# UPCNSL-ABS-FLS-RFS.net
KiCad netlist of a schematic drawn in Altium Designer
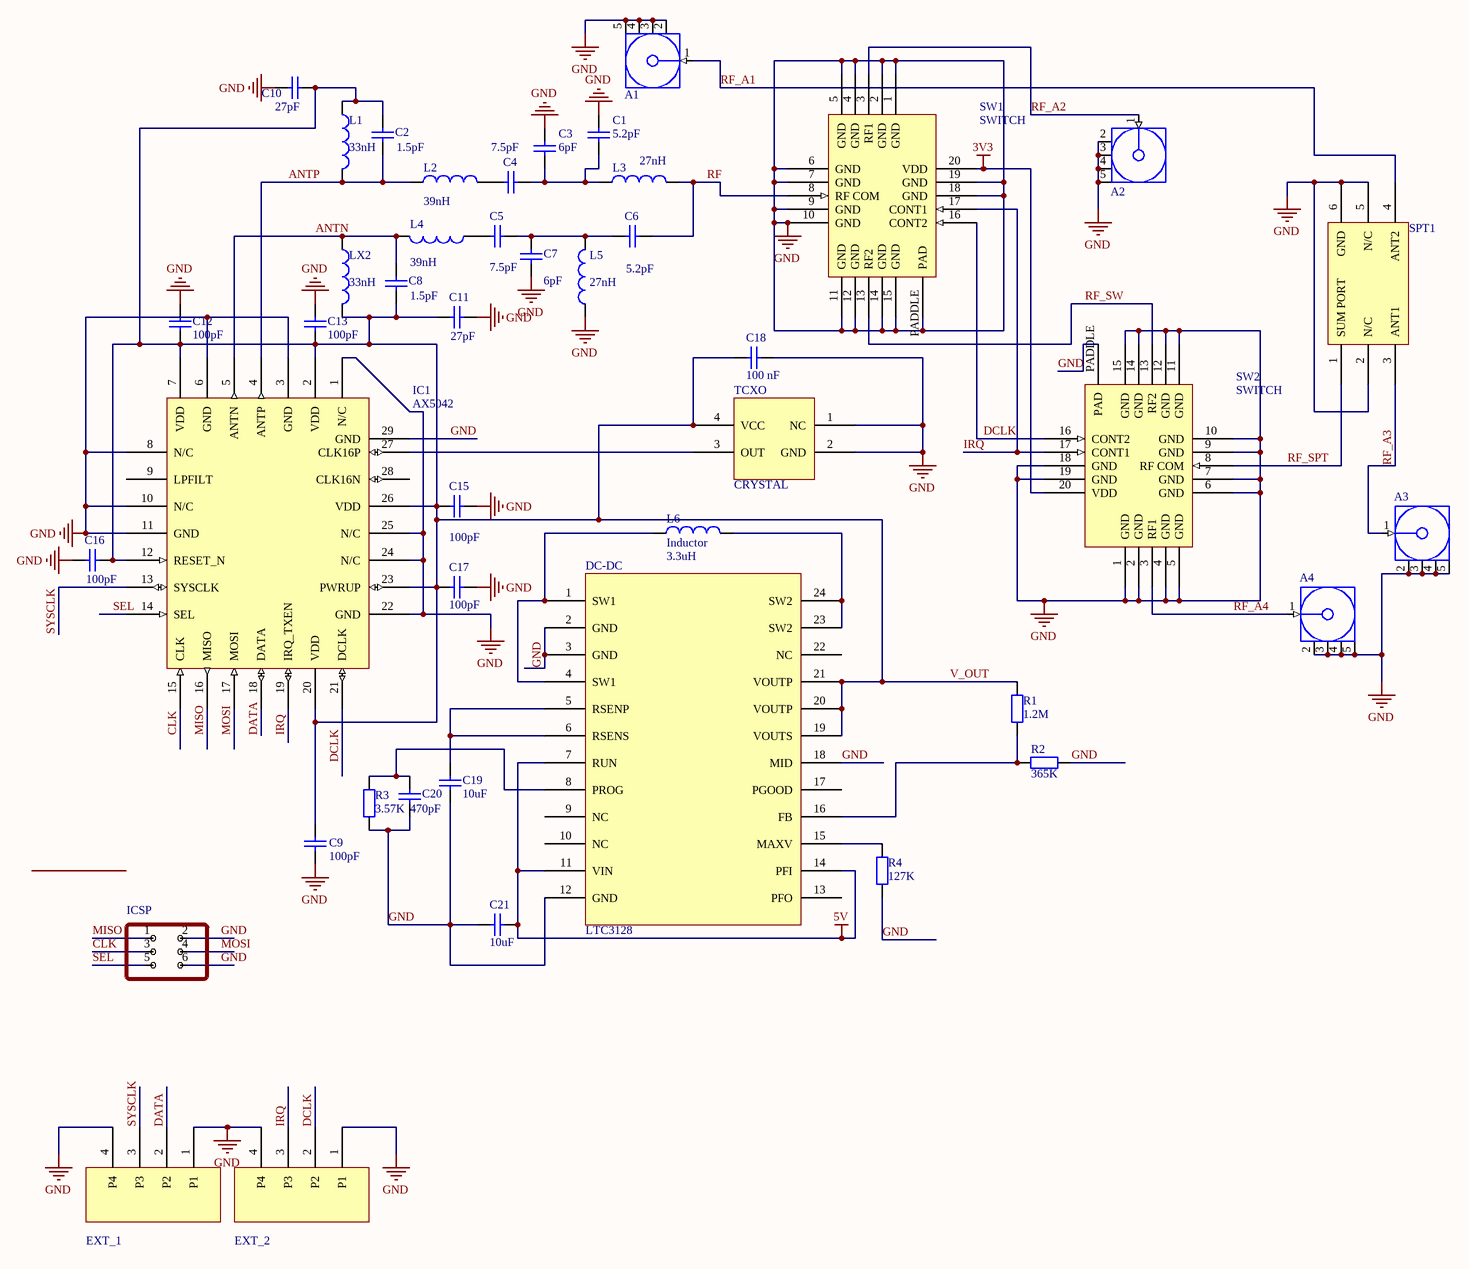
[diagram p0: UPCNSL-ABS-FLS-RFS.SchDoc]

(export (version "E")
  (design (tool "Eeschema 10.0.6"))
  (components
    (comp (ref "A1")
      (value "ANTENNA")
      (footprint "MCX5.08-H5")
      (fields (field (name "PUBLISHER") "Altium Limited"))
      (libsource (lib "Miscellaneous Connectors") (part "COAX-F"))
    )
    (comp (ref "A2")
      (value "SORTIDA AMP EXTERN")
      (footprint "MCX5.08-H5")
      (fields (field (name "PUBLISHER") "Altium Limited"))
      (libsource (lib "Miscellaneous Connectors") (part "COAX-F"))
    )
    (comp (ref "A3")
      (value "ANTENNA")
      (footprint "MCX5.08-H5")
      (fields (field (name "PUBLISHER") "Altium Limited"))
      (libsource (lib "Miscellaneous Connectors") (part "COAX-F"))
    )
    (comp (ref "A4")
      (value "ENTRADA AMP EXTERN")
      (footprint "MCX5.08-H5")
      (fields (field (name "PUBLISHER") "Altium Limited"))
      (libsource (lib "Miscellaneous Connectors") (part "COAX-F"))
    )
    (comp (ref "C1")
      (value "5.2pF")
      (footprint "CAP0603")
      (description "Capacitor")
      (fields (field (name "Comment") "CB1") (field (name "PUBLISHER") "Altium Limited"))
      (libsource (lib "Miscellaneous Devices") (part "Cap"))
    )
    (comp (ref "C2")
      (value "1.5pF")
      (footprint "CAP0603")
      (description "Capacitor")
      (fields (field (name "Comment") "CC1") (field (name "PUBLISHER") "Altium Limited"))
      (libsource (lib "Miscellaneous Devices") (part "Cap"))
    )
    (comp (ref "C3")
      (value "6pF")
      (footprint "CAP0603")
      (description "Capacitor")
      (fields (field (name "Comment") "CM1") (field (name "PUBLISHER") "Altium Limited"))
      (libsource (lib "Miscellaneous Devices") (part "Cap"))
    )
    (comp (ref "C4")
      (value "7.5pF")
      (footprint "CAP0603")
      (description "Capacitor")
      (fields (field (name "Comment") "CT1") (field (name "PUBLISHER") "Altium Limited"))
      (libsource (lib "Miscellaneous Devices") (part "Cap"))
    )
    (comp (ref "C5")
      (value "7.5pF")
      (footprint "CAP0603")
      (description "Capacitor")
      (fields (field (name "Comment") "CT2") (field (name "PUBLISHER") "Altium Limited"))
      (libsource (lib "Miscellaneous Devices") (part "Cap"))
    )
    (comp (ref "C6")
      (value "5.2pF")
      (footprint "CAP0603")
      (description "Capacitor")
      (fields (field (name "Comment") "CB2") (field (name "PUBLISHER") "Altium Limited"))
      (libsource (lib "Miscellaneous Devices") (part "Cap"))
    )
    (comp (ref "C7")
      (value "6pF")
      (footprint "CAP0603")
      (description "Capacitor")
      (fields (field (name "Comment") "CM2") (field (name "PUBLISHER") "Altium Limited"))
      (libsource (lib "Miscellaneous Devices") (part "Cap"))
    )
    (comp (ref "C8")
      (value "1.5pF")
      (footprint "CAP0603")
      (description "Capacitor")
      (fields (field (name "Comment") "CC2") (field (name "PUBLISHER") "Altium Limited"))
      (libsource (lib "Miscellaneous Devices") (part "Cap"))
    )
    (comp (ref "C9")
      (value "100pF")
      (footprint "CAP0603")
      (description "Capacitor")
      (fields (field (name "Comment") "CV1") (field (name "PUBLISHER") "Altium Limited"))
      (libsource (lib "Miscellaneous Devices") (part "Cap"))
    )
    (comp (ref "C10")
      (value "27pF")
      (footprint "CAP0603")
      (description "Capacitor")
      (fields (field (name "Comment") "Cap") (field (name "PUBLISHER") "Altium Limited"))
      (libsource (lib "Miscellaneous Devices") (part "Cap"))
    )
    (comp (ref "C11")
      (value "27pF")
      (footprint "CAP0603")
      (description "Capacitor")
      (fields (field (name "Comment") "Cap") (field (name "PUBLISHER") "Altium Limited"))
      (libsource (lib "Miscellaneous Devices") (part "Cap"))
    )
    (comp (ref "C12")
      (value "100pF")
      (footprint "CAP0603")
      (description "Capacitor")
      (fields (field (name "Comment") "Cap") (field (name "PUBLISHER") "Altium Limited"))
      (libsource (lib "Miscellaneous Devices") (part "Cap"))
    )
    (comp (ref "C13")
      (value "100pF")
      (footprint "CAP0603")
      (description "Capacitor")
      (fields (field (name "Comment") "Cap") (field (name "PUBLISHER") "Altium Limited"))
      (libsource (lib "Miscellaneous Devices") (part "Cap"))
    )
    (comp (ref "C15")
      (value "100pF")
      (footprint "CAP0603")
      (description "Capacitor")
      (fields (field (name "Comment") "Cap") (field (name "PUBLISHER") "Altium Limited"))
      (libsource (lib "Miscellaneous Devices") (part "Cap"))
    )
    (comp (ref "C16")
      (value "100pF")
      (footprint "CAP0603")
      (description "Capacitor")
      (fields (field (name "Comment") "Cap") (field (name "PUBLISHER") "Altium Limited"))
      (libsource (lib "Miscellaneous Devices") (part "Cap"))
    )
    (comp (ref "C17")
      (value "100pF")
      (footprint "CAP0603")
      (description "Capacitor")
      (fields (field (name "Comment") "Cap") (field (name "PUBLISHER") "Altium Limited"))
      (libsource (lib "Miscellaneous Devices") (part "Cap"))
    )
    (comp (ref "C18")
      (value "100 nF")
      (footprint "CAP0603")
      (description "Capacitor")
      (fields (field (name "Comment") "Cap") (field (name "PUBLISHER") "Altium Limited"))
      (libsource (lib "Miscellaneous Devices") (part "Cap"))
    )
    (comp (ref "C19")
      (value "10uF")
      (footprint "CAP0603")
      (description "Capacitor")
      (fields (field (name "Comment") "CAP0603"))
      (libsource (lib "UPCNSL-ABS-FLS-ARD_v1") (part "CAP0603"))
    )
    (comp (ref "C20")
      (value "470pF")
      (footprint "CAP0603")
      (description "Capacitor")
      (fields (field (name "Comment") "CAP0603"))
      (libsource (lib "UPCNSL-ABS-FLS-ARD_v1") (part "CAP0603"))
    )
    (comp (ref "C21")
      (value "10uF")
      (footprint "CAP0603")
      (description "Capacitor")
      (fields (field (name "Comment") "CAP0603"))
      (libsource (lib "UPCNSL-ABS-FLS-ARD_v1") (part "CAP0603"))
    )
    (comp (ref "DC-DC")
      (value "LTC3128")
      (footprint "DW024 (LTC3128)")
      (libsource (lib "UPCNSL-ABS-FLS-ARD_v1.2") (part "LTC3128"))
    )
    (comp (ref "EXT_1")
      (value "HEADER_CONNECTION")
      (footprint "HEADER_CONNECTION")
      (libsource (lib "UPCNSL-ABS-FLS-ARD_v1.2") (part "HEADER_CONNECTION"))
    )
    (comp (ref "EXT_2")
      (value "HEADER_CONNECTION")
      (footprint "HEADER_CONNECTION")
      (libsource (lib "UPCNSL-ABS-FLS-ARD_v1.2") (part "HEADER_CONNECTION"))
    )
    (comp (ref "IC1")
      (value "AX5042")
      (footprint "AX5042")
      (libsource (lib "UPCNSL-ABS-FLS-RFS") (part "AX5042"))
    )
    (comp (ref "ICSP")
      (value "3X2M")
      (footprint "Header 3x2")
      (description "PIN HEADER")
      (libsource (lib "UPCNSL-ABS-FLS-ARD_v1.2") (part "HEADER 3X2"))
    )
    (comp (ref "L1")
      (value "33nH")
      (footprint "INDUCTOR(1608)")
      (description "Inductor")
      (fields (field (name "Comment") "LX1") (field (name "PUBLISHER") "Altium Limited"))
      (libsource (lib "Miscellaneous Devices") (part "Inductor"))
    )
    (comp (ref "L2")
      (value "39nH")
      (footprint "INDUCTOR(1608)")
      (description "Inductor")
      (fields (field (name "Comment") "LT1") (field (name "PUBLISHER") "Altium Limited"))
      (libsource (lib "Miscellaneous Devices") (part "Inductor"))
    )
    (comp (ref "L3")
      (value "27nH")
      (footprint "INDUCTOR(1608)")
      (description "Inductor")
      (fields (field (name "Comment") "LB2") (field (name "PUBLISHER") "Altium Limited"))
      (libsource (lib "Miscellaneous Devices") (part "Inductor"))
    )
    (comp (ref "L4")
      (value "39nH")
      (footprint "INDUCTOR(1608)")
      (description "Inductor")
      (fields (field (name "Comment") "LT2") (field (name "PUBLISHER") "Altium Limited"))
      (libsource (lib "Miscellaneous Devices") (part "Inductor"))
    )
    (comp (ref "L5")
      (value "27nH")
      (footprint "INDUCTOR(1608)")
      (description "Inductor")
      (fields (field (name "Comment") "LB1") (field (name "PUBLISHER") "Altium Limited"))
      (libsource (lib "Miscellaneous Devices") (part "Inductor"))
    )
    (comp (ref "L6")
      (value "Inductor")
      (footprint "INDUCTOR(1608)")
      (fields (field (name "ALTIUM_VALUE") "3.3uH") (field (name "PUBLISHER") "Altium Limited"))
      (libsource (lib "Miscellaneous Devices") (part "Inductor"))
    )
    (comp (ref "LX2")
      (value "33nH")
      (footprint "INDUCTOR(1608)")
      (description "Inductor")
      (fields (field (name "Comment") "LX2") (field (name "PUBLISHER") "Altium Limited"))
      (libsource (lib "Miscellaneous Devices") (part "Inductor"))
    )
    (comp (ref "R1")
      (value "1.2M")
      (footprint "RES0603")
      (description "Resistor")
      (fields (field (name "Comment") "RES0603"))
      (libsource (lib "UPCNSL-ABS-FLS-ARD_v1") (part "RES0603"))
    )
    (comp (ref "R2")
      (value "365K")
      (footprint "RES0603")
      (description "Resistor")
      (fields (field (name "Comment") "RES0603"))
      (libsource (lib "") (part "RES0603_1"))
    )
    (comp (ref "R3")
      (value "3.57K")
      (footprint "RES0603")
      (description "Resistor")
      (fields (field (name "Comment") "RES0603"))
      (libsource (lib "UPCNSL-ABS-FLS-ARD_v1") (part "RES0603"))
    )
    (comp (ref "R4")
      (value "127K")
      (footprint "RES0603")
      (description "Resistor")
      (fields (field (name "Comment") "RES0603"))
      (libsource (lib "UPCNSL-ABS-FLS-ARD_v1") (part "RES0603"))
    )
    (comp (ref "SPT1")
      (value "2 Way -0º split")
      (footprint "SOTFL254P691X411-6N(splitter 2 way-0)")
      (description "Splitter with 0º phase")
      (libsource (lib "Splitters") (part "2 WAY-0º"))
    )
    (comp (ref "SW1")
      (value "SWITCH")
      (footprint "SWITCH")
      (libsource (lib "UPCNSL-ABS-FLS-RFS") (part "SWITCH"))
    )
    (comp (ref "SW2") (value "SWITCH") (footprint "SWITCH") (libsource (lib "") (part "SWITCH_1")))
    (comp (ref "TCXO")
      (value "CRYSTAL")
      (footprint "CRYSTAL TG-5006CJ-24L")
      (libsource (lib "UPCNSL-ABS-FLS-RFS") (part "CRYSTAL"))
    )
  )
  (nets
    (net (code "1") (name "/ANTN") (class "Default")
      (node (ref "C8") (pin "2") (pinfunction "2_2") (pintype "passive"))
      (node (ref "IC1") (pin "5") (pinfunction "ANTN_5") (pintype "output"))
      (node (ref "L4") (pin "2") (pinfunction "2_2") (pintype "passive"))
      (node (ref "LX2") (pin "1") (pinfunction "1_1") (pintype "passive"))
    )
    (net (code "2") (name "/ANTP") (class "Default")
      (node (ref "C2") (pin "1") (pinfunction "1_1") (pintype "passive"))
      (node (ref "IC1") (pin "4") (pinfunction "ANTP_4") (pintype "output"))
      (node (ref "L1") (pin "2") (pinfunction "2_2") (pintype "passive"))
      (node (ref "L2") (pin "1") (pinfunction "1_1") (pintype "passive"))
    )
    (net (code "3") (name "/CLK") (class "Default")
      (node (ref "IC1") (pin "15") (pinfunction "CLK_15") (pintype "input"))
      (node (ref "ICSP") (pin "3") (pinfunction "3_3") (pintype "passive"))
    )
    (net (code "4") (name "/DATA") (class "Default")
      (node (ref "EXT_1") (pin "2") (pinfunction "P2_2") (pintype "passive"))
      (node (ref "IC1") (pin "18") (pinfunction "DATA_18") (pintype "bidirectional"))
    )
    (net (code "5") (name "/DCLK") (class "Default")
      (node (ref "EXT_2") (pin "2") (pinfunction "P2_2") (pintype "passive"))
      (node (ref "IC1") (pin "21") (pinfunction "DCLK_21") (pintype "bidirectional"))
      (node (ref "SW1") (pin "16") (pinfunction "CONT2_16") (pintype "input"))
      (node (ref "SW2") (pin "16") (pinfunction "CONT2_16") (pintype "input"))
    )
    (net (code "6") (name "/IRQ") (class "Default")
      (node (ref "EXT_2") (pin "3") (pinfunction "P3_3") (pintype "passive"))
      (node (ref "IC1") (pin "19") (pinfunction "IRQ_TXEN_19") (pintype "bidirectional"))
      (node (ref "SW1") (pin "17") (pinfunction "CONT1_17") (pintype "input"))
      (node (ref "SW2") (pin "17") (pinfunction "CONT1_17") (pintype "input"))
    )
    (net (code "7") (name "/MISO") (class "Default")
      (node (ref "IC1") (pin "16") (pinfunction "MISO_16") (pintype "output"))
      (node (ref "ICSP") (pin "1") (pinfunction "1_1") (pintype "passive"))
    )
    (net (code "8") (name "/MOSI") (class "Default")
      (node (ref "IC1") (pin "17") (pinfunction "MOSI_17") (pintype "input"))
      (node (ref "ICSP") (pin "4") (pinfunction "4_4") (pintype "passive"))
    )
    (net (code "9") (name "/RF") (class "Default")
      (node (ref "C6") (pin "1") (pinfunction "1_1") (pintype "passive"))
      (node (ref "L3") (pin "2") (pinfunction "2_2") (pintype "passive"))
      (node (ref "SW1") (pin "8") (pinfunction "RF_COM_8") (pintype "input"))
    )
    (net (code "10") (name "/RF_A1") (class "Default")
      (node (ref "A1") (pin "1") (pinfunction "Signal_1") (pintype "input"))
      (node (ref "SPT1") (pin "4") (pinfunction "ANT2_4") (pintype "passive"))
    )
    (net (code "11") (name "/RF_A2") (class "Default")
      (node (ref "A2") (pin "1") (pinfunction "Signal_1") (pintype "input"))
      (node (ref "SW1") (pin "3") (pinfunction "RF1_3") (pintype "passive"))
    )
    (net (code "12") (name "/RF_A3") (class "Default")
      (node (ref "A3") (pin "1") (pinfunction "Signal_1") (pintype "input"))
      (node (ref "SPT1") (pin "3") (pinfunction "ANT1_3") (pintype "passive"))
    )
    (net (code "13") (name "/RF_A4") (class "Default")
      (node (ref "A4") (pin "1") (pinfunction "Signal_1") (pintype "input"))
      (node (ref "SW2") (pin "3") (pinfunction "RF1_3") (pintype "passive"))
    )
    (net (code "14") (name "/RF_SPT") (class "Default")
      (node (ref "SPT1") (pin "1") (pinfunction "SUM_PORT_1") (pintype "passive"))
      (node (ref "SW2") (pin "8") (pinfunction "RF_COM_8") (pintype "input"))
    )
    (net (code "15") (name "/RF_SW") (class "Default")
      (node (ref "SW1") (pin "13") (pinfunction "RF2_13") (pintype "passive"))
      (node (ref "SW2") (pin "13") (pinfunction "RF2_13") (pintype "passive"))
    )
    (net (code "16") (name "/SEL") (class "Default")
      (node (ref "IC1") (pin "14") (pinfunction "SEL_14") (pintype "input"))
      (node (ref "ICSP") (pin "5") (pinfunction "5_5") (pintype "passive"))
    )
    (net (code "17") (name "/SYSCLK") (class "Default")
      (node (ref "EXT_1") (pin "3") (pinfunction "P3_3") (pintype "passive"))
      (node (ref "IC1") (pin "13") (pinfunction "SYSCLK_13") (pintype "bidirectional"))
    )
    (net (code "18") (name "/V_OUT") (class "Default")
      (node (ref "C10") (pin "2") (pinfunction "2_2") (pintype "passive"))
      (node (ref "C11") (pin "1") (pinfunction "1_1") (pintype "passive"))
      (node (ref "C12") (pin "1") (pinfunction "1_1") (pintype "passive"))
      (node (ref "C13") (pin "1") (pinfunction "1_1") (pintype "passive"))
      (node (ref "C15") (pin "1") (pinfunction "1_1") (pintype "passive"))
      (node (ref "C16") (pin "2") (pinfunction "2_2") (pintype "passive"))
      (node (ref "C17") (pin "2") (pinfunction "2_2") (pintype "passive"))
      (node (ref "C18") (pin "2") (pinfunction "2_2") (pintype "passive"))
      (node (ref "C2") (pin "2") (pinfunction "2_2") (pintype "passive"))
      (node (ref "C8") (pin "1") (pinfunction "1_1") (pintype "passive"))
      (node (ref "C9") (pin "2") (pinfunction "2_2") (pintype "passive"))
      (node (ref "DC-DC") (pin "19") (pinfunction "VOUTS_19") (pintype "passive"))
      (node (ref "DC-DC") (pin "20") (pinfunction "VOUTP_20") (pintype "passive"))
      (node (ref "DC-DC") (pin "21") (pinfunction "VOUTP_21") (pintype "passive"))
      (node (ref "IC1") (pin "12") (pinfunction "RESET_N_12") (pintype "input"))
      (node (ref "IC1") (pin "2") (pinfunction "VDD_2") (pintype "power_in"))
      (node (ref "IC1") (pin "20") (pinfunction "VDD_20") (pintype "power_in"))
      (node (ref "IC1") (pin "23") (pinfunction "PWRUP_23") (pintype "bidirectional"))
      (node (ref "IC1") (pin "26") (pinfunction "VDD_26") (pintype "power_in"))
      (node (ref "IC1") (pin "7") (pinfunction "VDD_7") (pintype "power_in"))
      (node (ref "L1") (pin "1") (pinfunction "1_1") (pintype "passive"))
      (node (ref "LX2") (pin "2") (pinfunction "2_2") (pintype "passive"))
      (node (ref "R1") (pin "2") (pinfunction "2_2") (pintype "passive"))
      (node (ref "TCXO") (pin "4") (pinfunction "VCC_4") (pintype "passive"))
    )
    (net (code "19") (name "3V3") (class "Default")
      (node (ref "SW1") (pin "20") (pinfunction "VDD_20") (pintype "power_in"))
      (node (ref "SW2") (pin "20") (pinfunction "VDD_20") (pintype "power_in"))
    )
    (net (code "20") (name "5V") (class "Default")
      (node (ref "C21") (pin "1") (pinfunction "1_1") (pintype "passive"))
      (node (ref "DC-DC") (pin "11") (pinfunction "VIN_11") (pintype "passive"))
      (node (ref "DC-DC") (pin "14") (pinfunction "PFI_14") (pintype "passive"))
      (node (ref "DC-DC") (pin "7") (pinfunction "RUN_7") (pintype "passive"))
    )
    (net (code "21") (name "GND") (class "Default")
      (node (ref "A1") (pin "2") (pinfunction "GND_2") (pintype "power_in"))
      (node (ref "A1") (pin "3") (pinfunction "GND_3") (pintype "power_in"))
      (node (ref "A1") (pin "4") (pinfunction "GND_4") (pintype "power_in"))
      (node (ref "A1") (pin "5") (pinfunction "GND_5") (pintype "power_in"))
      (node (ref "A2") (pin "2") (pinfunction "GND_2") (pintype "power_in"))
      (node (ref "A2") (pin "3") (pinfunction "GND_3") (pintype "power_in"))
      (node (ref "A2") (pin "4") (pinfunction "GND_4") (pintype "power_in"))
      (node (ref "A2") (pin "5") (pinfunction "GND_5") (pintype "power_in"))
      (node (ref "A3") (pin "2") (pinfunction "GND_2") (pintype "power_in"))
      (node (ref "A3") (pin "3") (pinfunction "GND_3") (pintype "power_in"))
      (node (ref "A3") (pin "4") (pinfunction "GND_4") (pintype "power_in"))
      (node (ref "A3") (pin "5") (pinfunction "GND_5") (pintype "power_in"))
      (node (ref "A4") (pin "2") (pinfunction "GND_2") (pintype "power_in"))
      (node (ref "A4") (pin "3") (pinfunction "GND_3") (pintype "power_in"))
      (node (ref "A4") (pin "4") (pinfunction "GND_4") (pintype "power_in"))
      (node (ref "A4") (pin "5") (pinfunction "GND_5") (pintype "power_in"))
      (node (ref "C1") (pin "2") (pinfunction "2_2") (pintype "passive"))
      (node (ref "C10") (pin "1") (pinfunction "1_1") (pintype "passive"))
      (node (ref "C11") (pin "2") (pinfunction "2_2") (pintype "passive"))
      (node (ref "C12") (pin "2") (pinfunction "2_2") (pintype "passive"))
      (node (ref "C13") (pin "2") (pinfunction "2_2") (pintype "passive"))
      (node (ref "C15") (pin "2") (pinfunction "2_2") (pintype "passive"))
      (node (ref "C16") (pin "1") (pinfunction "1_1") (pintype "passive"))
      (node (ref "C17") (pin "1") (pinfunction "1_1") (pintype "passive"))
      (node (ref "C18") (pin "1") (pinfunction "1_1") (pintype "passive"))
      (node (ref "C19") (pin "1") (pinfunction "1_1") (pintype "passive"))
      (node (ref "C20") (pin "1") (pinfunction "1_1") (pintype "passive"))
      (node (ref "C21") (pin "2") (pinfunction "2_2") (pintype "passive"))
      (node (ref "C3") (pin "2") (pinfunction "2_2") (pintype "passive"))
      (node (ref "C7") (pin "2") (pinfunction "2_2") (pintype "passive"))
      (node (ref "C9") (pin "1") (pinfunction "1_1") (pintype "passive"))
      (node (ref "DC-DC") (pin "12") (pinfunction "GND_12") (pintype "passive"))
      (node (ref "DC-DC") (pin "18") (pinfunction "MID_18") (pintype "passive"))
      (node (ref "DC-DC") (pin "2") (pinfunction "GND_2") (pintype "passive"))
      (node (ref "DC-DC") (pin "3") (pinfunction "GND_3") (pintype "passive"))
      (node (ref "EXT_1") (pin "1") (pinfunction "P1_1") (pintype "passive"))
      (node (ref "EXT_1") (pin "4") (pinfunction "P4_4") (pintype "passive"))
      (node (ref "EXT_2") (pin "1") (pinfunction "P1_1") (pintype "passive"))
      (node (ref "EXT_2") (pin "4") (pinfunction "P4_4") (pintype "passive"))
      (node (ref "IC1") (pin "1") (pinfunction "N/C_1") (pintype "passive"))
      (node (ref "IC1") (pin "10") (pinfunction "N/C_10") (pintype "passive"))
      (node (ref "IC1") (pin "11") (pinfunction "GND_11") (pintype "power_in"))
      (node (ref "IC1") (pin "22") (pinfunction "GND_22") (pintype "power_in"))
      (node (ref "IC1") (pin "24") (pinfunction "N/C_24") (pintype "passive"))
      (node (ref "IC1") (pin "25") (pinfunction "N/C_25") (pintype "passive"))
      (node (ref "IC1") (pin "29") (pinfunction "GND_29") (pintype "passive"))
      (node (ref "IC1") (pin "3") (pinfunction "GND_3") (pintype "power_in"))
      (node (ref "IC1") (pin "6") (pinfunction "GND_6") (pintype "power_in"))
      (node (ref "IC1") (pin "8") (pinfunction "N/C_8") (pintype "passive"))
      (node (ref "ICSP") (pin "2") (pinfunction "2_2") (pintype "passive"))
      (node (ref "ICSP") (pin "6") (pinfunction "6_6") (pintype "passive"))
      (node (ref "L5") (pin "1") (pinfunction "1_1") (pintype "passive"))
      (node (ref "R2") (pin "1") (pinfunction "1_1") (pintype "passive"))
      (node (ref "R3") (pin "1") (pinfunction "1_1") (pintype "passive"))
      (node (ref "R4") (pin "1") (pinfunction "1_1") (pintype "passive"))
      (node (ref "SPT1") (pin "2") (pinfunction "N/C_2") (pintype "passive"))
      (node (ref "SPT1") (pin "5") (pinfunction "N/C_5") (pintype "passive"))
      (node (ref "SPT1") (pin "6") (pinfunction "GND_6") (pintype "passive"))
      (node (ref "SW1") (pin "1") (pinfunction "GND_1") (pintype "power_in"))
      (node (ref "SW1") (pin "10") (pinfunction "GND_10") (pintype "power_in"))
      (node (ref "SW1") (pin "11") (pinfunction "GND_11") (pintype "power_in"))
      (node (ref "SW1") (pin "12") (pinfunction "GND_12") (pintype "power_in"))
      (node (ref "SW1") (pin "14") (pinfunction "GND_14") (pintype "power_in"))
      (node (ref "SW1") (pin "15") (pinfunction "GND_15") (pintype "power_in"))
      (node (ref "SW1") (pin "18") (pinfunction "GND_18") (pintype "power_in"))
      (node (ref "SW1") (pin "19") (pinfunction "GND_19") (pintype "power_in"))
      (node (ref "SW1") (pin "2") (pinfunction "GND_2") (pintype "power_in"))
      (node (ref "SW1") (pin "4") (pinfunction "GND_4") (pintype "power_in"))
      (node (ref "SW1") (pin "5") (pinfunction "GND_5") (pintype "power_in"))
      (node (ref "SW1") (pin "6") (pinfunction "GND_6") (pintype "power_in"))
      (node (ref "SW1") (pin "7") (pinfunction "GND_7") (pintype "power_in"))
      (node (ref "SW1") (pin "9") (pinfunction "GND_9") (pintype "power_in"))
      (node (ref "SW1") (pin "PADDLE") (pinfunction "PAD_PADDLE") (pintype "passive"))
      (node (ref "SW2") (pin "1") (pinfunction "GND_1") (pintype "power_in"))
      (node (ref "SW2") (pin "10") (pinfunction "GND_10") (pintype "power_in"))
      (node (ref "SW2") (pin "11") (pinfunction "GND_11") (pintype "power_in"))
      (node (ref "SW2") (pin "12") (pinfunction "GND_12") (pintype "power_in"))
      (node (ref "SW2") (pin "14") (pinfunction "GND_14") (pintype "power_in"))
      (node (ref "SW2") (pin "15") (pinfunction "GND_15") (pintype "power_in"))
      (node (ref "SW2") (pin "18") (pinfunction "GND_18") (pintype "power_in"))
      (node (ref "SW2") (pin "19") (pinfunction "GND_19") (pintype "power_in"))
      (node (ref "SW2") (pin "2") (pinfunction "GND_2") (pintype "power_in"))
      (node (ref "SW2") (pin "4") (pinfunction "GND_4") (pintype "power_in"))
      (node (ref "SW2") (pin "5") (pinfunction "GND_5") (pintype "power_in"))
      (node (ref "SW2") (pin "6") (pinfunction "GND_6") (pintype "power_in"))
      (node (ref "SW2") (pin "7") (pinfunction "GND_7") (pintype "power_in"))
      (node (ref "SW2") (pin "9") (pinfunction "GND_9") (pintype "power_in"))
      (node (ref "SW2") (pin "PADDLE") (pinfunction "PAD_PADDLE") (pintype "passive"))
      (node (ref "TCXO") (pin "1") (pinfunction "NC_1") (pintype "passive"))
      (node (ref "TCXO") (pin "2") (pinfunction "GND_2") (pintype "passive"))
    )
    (net (code "22") (name "Net-(C1-Pad1)") (class "Default")
      (node (ref "C1") (pin "1") (pinfunction "1_1") (pintype "passive"))
      (node (ref "C3") (pin "1") (pinfunction "1_1") (pintype "passive"))
      (node (ref "C4") (pin "1") (pinfunction "1_1") (pintype "passive"))
      (node (ref "L3") (pin "1") (pinfunction "1_1") (pintype "passive"))
    )
    (net (code "23") (name "Net-(C4-Pad2)") (class "Default")
      (node (ref "C4") (pin "2") (pinfunction "2_2") (pintype "passive"))
      (node (ref "L2") (pin "2") (pinfunction "2_2") (pintype "passive"))
    )
    (net (code "24") (name "Net-(C5-Pad1)") (class "Default")
      (node (ref "C5") (pin "1") (pinfunction "1_1") (pintype "passive"))
      (node (ref "C6") (pin "2") (pinfunction "2_2") (pintype "passive"))
      (node (ref "C7") (pin "1") (pinfunction "1_1") (pintype "passive"))
      (node (ref "L5") (pin "2") (pinfunction "2_2") (pintype "passive"))
    )
    (net (code "25") (name "Net-(C5-Pad2)") (class "Default")
      (node (ref "C5") (pin "2") (pinfunction "2_2") (pintype "passive"))
      (node (ref "L4") (pin "1") (pinfunction "1_1") (pintype "passive"))
    )
    (net (code "26") (name "Net-(DC-DC-FB)") (class "Default")
      (node (ref "DC-DC") (pin "16") (pinfunction "FB_16") (pintype "passive"))
      (node (ref "R1") (pin "1") (pinfunction "1_1") (pintype "passive"))
      (node (ref "R2") (pin "2") (pinfunction "2_2") (pintype "passive"))
    )
    (net (code "27") (name "Net-(DC-DC-MAXV)") (class "Default")
      (node (ref "DC-DC") (pin "15") (pinfunction "MAXV_15") (pintype "passive"))
      (node (ref "R4") (pin "2") (pinfunction "2_2") (pintype "passive"))
    )
    (net (code "28") (name "Net-(DC-DC-PROG)") (class "Default")
      (node (ref "C20") (pin "2") (pinfunction "2_2") (pintype "passive"))
      (node (ref "DC-DC") (pin "8") (pinfunction "PROG_8") (pintype "passive"))
      (node (ref "R3") (pin "2") (pinfunction "2_2") (pintype "passive"))
    )
    (net (code "29") (name "Net-(DC-DC-RSENP)") (class "Default")
      (node (ref "C19") (pin "2") (pinfunction "2_2") (pintype "passive"))
      (node (ref "DC-DC") (pin "5") (pinfunction "RSENP_5") (pintype "passive"))
      (node (ref "DC-DC") (pin "6") (pinfunction "RSENS_6") (pintype "passive"))
    )
    (net (code "30") (name "Net-(DC-DC-SW1-Pad1)") (class "Default")
      (node (ref "DC-DC") (pin "1") (pinfunction "SW1_1") (pintype "passive"))
      (node (ref "DC-DC") (pin "4") (pinfunction "SW1_4") (pintype "passive"))
      (node (ref "L6") (pin "1") (pinfunction "1_1") (pintype "passive"))
    )
    (net (code "31") (name "Net-(DC-DC-SW2-Pad23)") (class "Default")
      (node (ref "DC-DC") (pin "23") (pinfunction "SW2_23") (pintype "passive"))
      (node (ref "DC-DC") (pin "24") (pinfunction "SW2_24") (pintype "passive"))
      (node (ref "L6") (pin "2") (pinfunction "2_2") (pintype "passive"))
    )
    (net (code "32") (name "Net-(IC1-CLK16P)") (class "Default")
      (node (ref "IC1") (pin "27") (pinfunction "CLK16P_27") (pintype "bidirectional"))
      (node (ref "TCXO") (pin "3") (pinfunction "OUT_3") (pintype "passive"))
    )
    (net (code "33") (name "unconnected-(DC-DC-NC-Pad9)") (class "Default")
      (node (ref "DC-DC") (pin "9") (pinfunction "NC_9") (pintype "passive"))
    )
    (net (code "34") (name "unconnected-(DC-DC-NC-Pad10)") (class "Default")
      (node (ref "DC-DC") (pin "10") (pinfunction "NC_10") (pintype "passive"))
    )
    (net (code "35") (name "unconnected-(DC-DC-NC-Pad22)") (class "Default")
      (node (ref "DC-DC") (pin "22") (pinfunction "NC_22") (pintype "passive"))
    )
    (net (code "36") (name "unconnected-(DC-DC-PFO-Pad13)") (class "Default")
      (node (ref "DC-DC") (pin "13") (pinfunction "PFO_13") (pintype "passive"))
    )
    (net (code "37") (name "unconnected-(DC-DC-PGOOD-Pad17)") (class "Default")
      (node (ref "DC-DC") (pin "17") (pinfunction "PGOOD_17") (pintype "passive"))
    )
    (net (code "38") (name "unconnected-(IC1-CLK16N-Pad28)") (class "Default")
      (node (ref "IC1") (pin "28") (pinfunction "CLK16N_28") (pintype "bidirectional"))
    )
    (net (code "39") (name "unconnected-(IC1-LPFILT-Pad9)") (class "Default")
      (node (ref "IC1") (pin "9") (pinfunction "LPFILT_9") (pintype "passive"))
    )
  )
)
